# 4_Relays_Shutdown_TSAL.net
KiCad netlist of a schematic drawn in Altium Designer
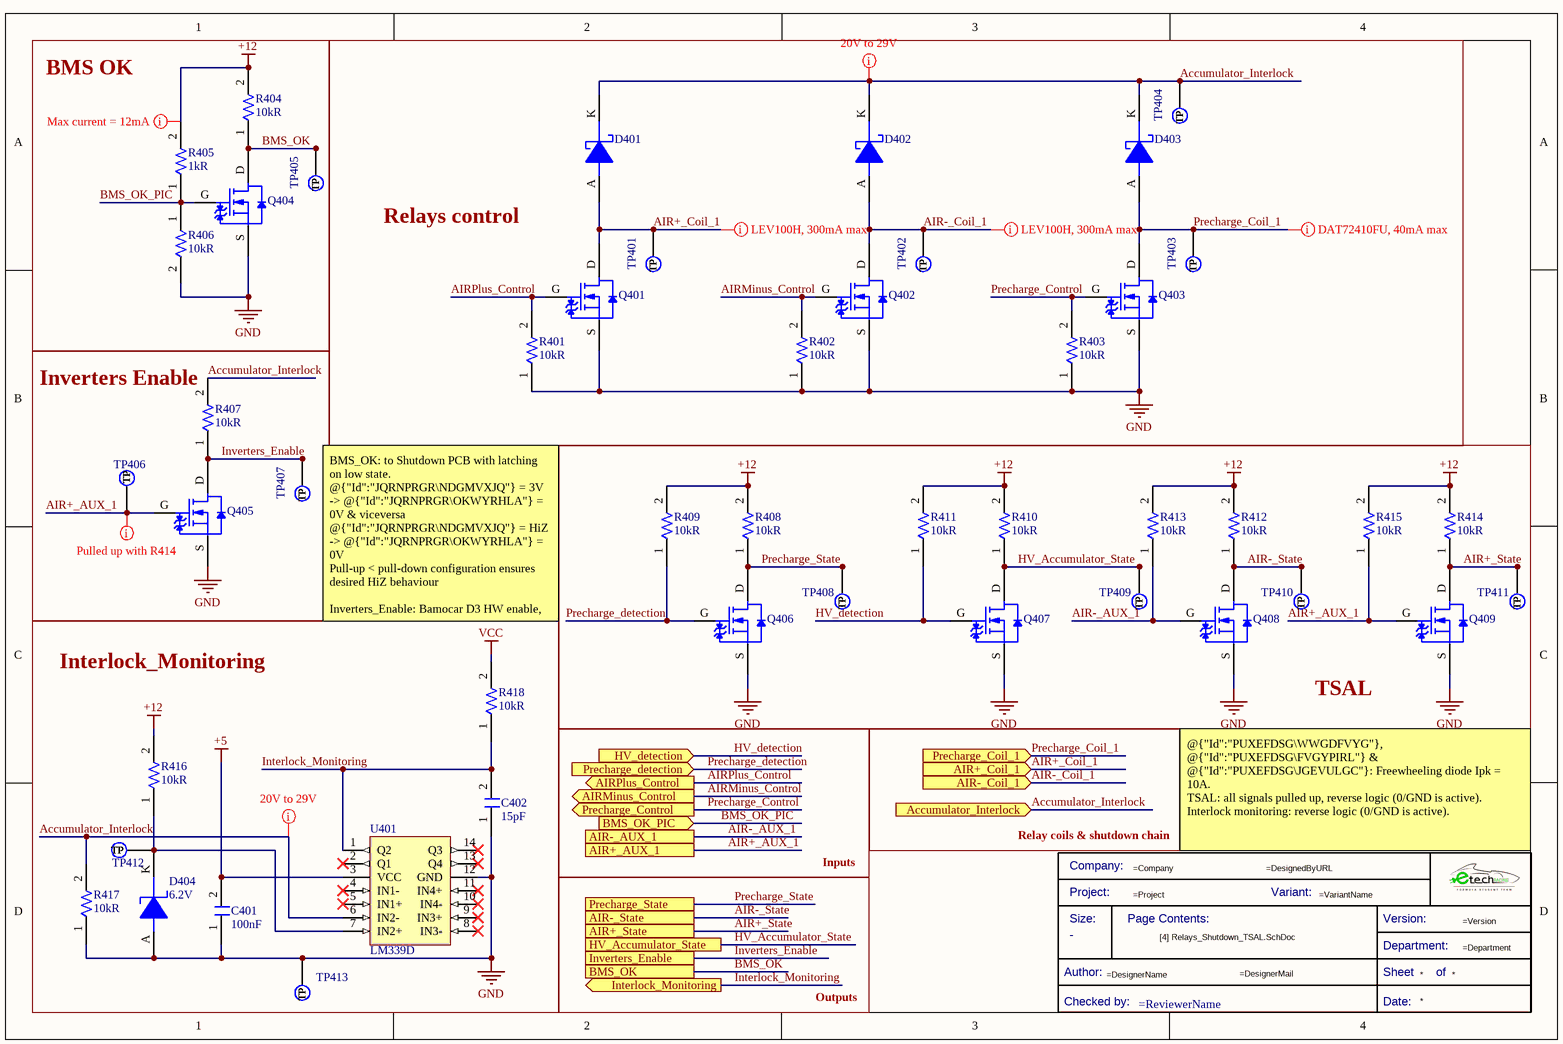
[diagram p0: [4] Relays_Shutdown_TSAL.SchDoc]

(export (version "E")
  (design (tool "Eeschema 10.0.6"))
  (components
    (comp (ref "*")
      (value "Title Block_template")
      (description "Standard Title Block")
      (fields (field (name "SIZE") "-"))
      (libsource (lib "e-Tech_Racing") (part "Title Block_template"))
    )
    (comp (ref "C401")
      (value "885012207098")
      (footprint "C0805FNPC-R")
      (description "Cap, 0.1ΜF, 50V, 10%, X7R, 0805")
      (fields
        (field (name "TOLERANCE") "10%")
        (field (name "CAPACITANCE") "100nF")
        (field (name ".CREATOR") "DR")
      )
      (libsource (lib "Passives") (part "C100n-50V-0805FNPC-X7R"))
    )
    (comp (ref "C402")
      (value "885012007052")
      (footprint "C0805FNPC-R")
      (description "Cap, 15PF, 50V, 5%, C0G/NP0, 0805")
      (fields
        (field (name "TOLERANCE") "5%")
        (field (name "CAPACITANCE") "15pF")
        (field (name ".CREATOR") "DR")
      )
      (libsource (lib "Passives") (part "C15p-50V-0805FNPC-NP0"))
    )
    (comp (ref "D401")
      (value "MBR0530")
      (footprint "DSC-SOD123")
      (description "VR=30V IF=500mA 30pF P=410mW")
      (fields (field (name ".CREATOR") "GP"))
      (libsource (lib "Filter components") (part "DSC-0.5/30-SOD123"))
    )
    (comp (ref "D402")
      (value "MBR0530")
      (footprint "DSC-SOD123")
      (description "VR=30V IF=500mA 30pF P=410mW")
      (fields (field (name ".CREATOR") "GP"))
      (libsource (lib "Filter components") (part "DSC-0.5/30-SOD123"))
    )
    (comp (ref "D403")
      (value "MBR0530")
      (footprint "DSC-SOD123")
      (description "VR=30V IF=500mA 30pF P=410mW")
      (fields (field (name ".CREATOR") "GP"))
      (libsource (lib "Filter components") (part "DSC-0.5/30-SOD123"))
    )
    (comp (ref "D404")
      (value "BZG05C6V2-E3-TR")
      (footprint "DZ-6.2V-DO-214AC")
      (description "BZG05C Series 6.2 V 200 mA Surface Mount Zener Diode - DO-214AC")
      (fields
        (field (name "TOLERANCE") "5%")
        (field (name "ZENER VOLTAGE") "6.2V")
        (field (name ".CREATOR") "DO")
      )
      (libsource (lib "Semiconductor") (part "DZ-6.2V-DO-214AC"))
    )
    (comp (ref "Q401")
      (value "CPH3455-TL-H")
      (footprint "TRT-NCH-3/35-CPH")
      (description "CPH3455-TL-H N-channel MOSFET Transistor; 3 A; 35 V; 3-Pin CPH")
      (fields (field (name "MANUFACTURER") "ON Semiconductor") (field (name ".CREATOR") "GP"))
      (libsource (lib "Semiconductor") (part "TRT-NCH-3/35-CPH"))
    )
    (comp (ref "Q402")
      (value "CPH3455-TL-H")
      (footprint "TRT-NCH-3/35-CPH")
      (description "CPH3455-TL-H N-channel MOSFET Transistor; 3 A; 35 V; 3-Pin CPH")
      (fields (field (name "MANUFACTURER") "ON Semiconductor") (field (name ".CREATOR") "GP"))
      (libsource (lib "Semiconductor") (part "TRT-NCH-3/35-CPH"))
    )
    (comp (ref "Q403")
      (value "CPH3455-TL-H")
      (footprint "TRT-NCH-3/35-CPH")
      (description "CPH3455-TL-H N-channel MOSFET Transistor; 3 A; 35 V; 3-Pin CPH")
      (fields (field (name "MANUFACTURER") "ON Semiconductor") (field (name ".CREATOR") "GP"))
      (libsource (lib "Semiconductor") (part "TRT-NCH-3/35-CPH"))
    )
    (comp (ref "Q404")
      (value "CPH3455-TL-H")
      (footprint "TRT-NCH-3/35-CPH")
      (description "CPH3455-TL-H N-channel MOSFET Transistor; 3 A; 35 V; 3-Pin CPH")
      (fields (field (name "MANUFACTURER") "ON Semiconductor") (field (name ".CREATOR") "GP"))
      (libsource (lib "Semiconductor") (part "TRT-NCH-3/35-CPH"))
    )
    (comp (ref "Q405")
      (value "CPH3455-TL-H")
      (footprint "TRT-NCH-3/35-CPH")
      (description "CPH3455-TL-H N-channel MOSFET Transistor; 3 A; 35 V; 3-Pin CPH")
      (fields (field (name "MANUFACTURER") "ON Semiconductor") (field (name ".CREATOR") "GP"))
      (libsource (lib "Semiconductor") (part "TRT-NCH-3/35-CPH"))
    )
    (comp (ref "Q406")
      (value "CPH3455-TL-H")
      (footprint "TRT-NCH-3/35-CPH")
      (description "CPH3455-TL-H N-channel MOSFET Transistor; 3 A; 35 V; 3-Pin CPH")
      (fields (field (name "MANUFACTURER") "ON Semiconductor") (field (name ".CREATOR") "GP"))
      (libsource (lib "Semiconductor") (part "TRT-NCH-3/35-CPH"))
    )
    (comp (ref "Q407")
      (value "CPH3455-TL-H")
      (footprint "TRT-NCH-3/35-CPH")
      (description "CPH3455-TL-H N-channel MOSFET Transistor; 3 A; 35 V; 3-Pin CPH")
      (fields (field (name "MANUFACTURER") "ON Semiconductor") (field (name ".CREATOR") "GP"))
      (libsource (lib "Semiconductor") (part "TRT-NCH-3/35-CPH"))
    )
    (comp (ref "Q408")
      (value "CPH3455-TL-H")
      (footprint "TRT-NCH-3/35-CPH")
      (description "CPH3455-TL-H N-channel MOSFET Transistor; 3 A; 35 V; 3-Pin CPH")
      (fields (field (name "MANUFACTURER") "ON Semiconductor") (field (name ".CREATOR") "GP"))
      (libsource (lib "Semiconductor") (part "TRT-NCH-3/35-CPH"))
    )
    (comp (ref "Q409")
      (value "CPH3455-TL-H")
      (footprint "TRT-NCH-3/35-CPH")
      (description "CPH3455-TL-H N-channel MOSFET Transistor; 3 A; 35 V; 3-Pin CPH")
      (fields (field (name "MANUFACTURER") "ON Semiconductor") (field (name ".CREATOR") "GP"))
      (libsource (lib "Semiconductor") (part "TRT-NCH-3/35-CPH"))
    )
    (comp (ref "R401")
      (value "CR0805-JW-103ELF")
      (footprint "R0805FTK")
      (fields
        (field (name "TOLERANCE") "5%")
        (field (name "RESISTANCE") "10kR")
        (field (name ".CREATOR") "DR")
      )
      (libsource (lib "Passives") (part "R10k-0805FTK"))
    )
    (comp (ref "R402")
      (value "CR0805-JW-103ELF")
      (footprint "R0805FTK")
      (fields
        (field (name "TOLERANCE") "5%")
        (field (name "RESISTANCE") "10kR")
        (field (name ".CREATOR") "DR")
      )
      (libsource (lib "Passives") (part "R10k-0805FTK"))
    )
    (comp (ref "R403")
      (value "CR0805-JW-103ELF")
      (footprint "R0805FTK")
      (fields
        (field (name "TOLERANCE") "5%")
        (field (name "RESISTANCE") "10kR")
        (field (name ".CREATOR") "DR")
      )
      (libsource (lib "Passives") (part "R10k-0805FTK"))
    )
    (comp (ref "R404")
      (value "CR0805-JW-103ELF")
      (footprint "R0805FTK")
      (fields
        (field (name "TOLERANCE") "5%")
        (field (name "RESISTANCE") "10kR")
        (field (name ".CREATOR") "DR")
      )
      (libsource (lib "Passives") (part "R10k-0805FTK"))
    )
    (comp (ref "R405")
      (value "CR0805-JW-102ELF")
      (footprint "R0805FTK")
      (description "Res Thick Film 0805 1K Ohm 5% 1/8W ±200ppm/°C Molded SMD SMD Paper Tape on Plastic Reel")
      (fields
        (field (name "TOLERANCE") "5%")
        (field (name "RESISTANCE") "1kR")
        (field (name ".CREATOR") "GP")
      )
      (libsource (lib "Passives") (part "R1k-0805FTK"))
    )
    (comp (ref "R406")
      (value "CR0805-JW-103ELF")
      (footprint "R0805FTK")
      (fields
        (field (name "TOLERANCE") "5%")
        (field (name "RESISTANCE") "10kR")
        (field (name ".CREATOR") "DR")
      )
      (libsource (lib "Passives") (part "R10k-0805FTK"))
    )
    (comp (ref "R407")
      (value "CR0805-JW-103ELF")
      (footprint "R0805FTK")
      (fields
        (field (name "TOLERANCE") "5%")
        (field (name "RESISTANCE") "10kR")
        (field (name ".CREATOR") "DR")
      )
      (libsource (lib "Passives") (part "R10k-0805FTK"))
    )
    (comp (ref "R408")
      (value "CR0805-JW-103ELF")
      (footprint "R0805FTK")
      (fields
        (field (name "TOLERANCE") "5%")
        (field (name "RESISTANCE") "10kR")
        (field (name ".CREATOR") "DR")
      )
      (libsource (lib "Passives") (part "R10k-0805FTK"))
    )
    (comp (ref "R409")
      (value "CR0805-JW-103ELF")
      (footprint "R0805FTK")
      (fields
        (field (name "TOLERANCE") "5%")
        (field (name "RESISTANCE") "10kR")
        (field (name ".CREATOR") "DR")
      )
      (libsource (lib "Passives") (part "R10k-0805FTK"))
    )
    (comp (ref "R410")
      (value "CR0805-JW-103ELF")
      (footprint "R0805FTK")
      (fields
        (field (name "TOLERANCE") "5%")
        (field (name "RESISTANCE") "10kR")
        (field (name ".CREATOR") "DR")
      )
      (libsource (lib "Passives") (part "R10k-0805FTK"))
    )
    (comp (ref "R411")
      (value "CR0805-JW-103ELF")
      (footprint "R0805FTK")
      (fields
        (field (name "TOLERANCE") "5%")
        (field (name "RESISTANCE") "10kR")
        (field (name ".CREATOR") "DR")
      )
      (libsource (lib "Passives") (part "R10k-0805FTK"))
    )
    (comp (ref "R412")
      (value "CR0805-JW-103ELF")
      (footprint "R0805FTK")
      (fields
        (field (name "TOLERANCE") "5%")
        (field (name "RESISTANCE") "10kR")
        (field (name ".CREATOR") "DR")
      )
      (libsource (lib "Passives") (part "R10k-0805FTK"))
    )
    (comp (ref "R413")
      (value "CR0805-JW-103ELF")
      (footprint "R0805FTK")
      (fields
        (field (name "TOLERANCE") "5%")
        (field (name "RESISTANCE") "10kR")
        (field (name ".CREATOR") "DR")
      )
      (libsource (lib "Passives") (part "R10k-0805FTK"))
    )
    (comp (ref "R414")
      (value "CR0805-JW-103ELF")
      (footprint "R0805FTK")
      (fields
        (field (name "TOLERANCE") "5%")
        (field (name "RESISTANCE") "10kR")
        (field (name ".CREATOR") "DR")
      )
      (libsource (lib "Passives") (part "R10k-0805FTK"))
    )
    (comp (ref "R415")
      (value "CR0805-JW-103ELF")
      (footprint "R0805FTK")
      (fields
        (field (name "TOLERANCE") "5%")
        (field (name "RESISTANCE") "10kR")
        (field (name ".CREATOR") "DR")
      )
      (libsource (lib "Passives") (part "R10k-0805FTK"))
    )
    (comp (ref "R416")
      (value "CR0805-JW-103ELF")
      (footprint "R0805FTK")
      (fields
        (field (name "TOLERANCE") "5%")
        (field (name "RESISTANCE") "10kR")
        (field (name ".CREATOR") "DR")
      )
      (libsource (lib "Passives") (part "R10k-0805FTK"))
    )
    (comp (ref "R417")
      (value "CR0805-JW-103ELF")
      (footprint "R0805FTK")
      (fields
        (field (name "TOLERANCE") "5%")
        (field (name "RESISTANCE") "10kR")
        (field (name ".CREATOR") "DR")
      )
      (libsource (lib "Passives") (part "R10k-0805FTK"))
    )
    (comp (ref "R418")
      (value "CR0805-JW-103ELF")
      (footprint "R0805FTK")
      (fields
        (field (name "TOLERANCE") "5%")
        (field (name "RESISTANCE") "10kR")
        (field (name ".CREATOR") "DR")
      )
      (libsource (lib "Passives") (part "R10k-0805FTK"))
    )
    (comp (ref "TP401")
      (value "TestPoint")
      (footprint "TestPoint")
      (description "Test Point 1x1 mm")
      (fields (field (name ".CREATOR") "GP") (field (name ".PCBCHECK") "GP") (field (name ".SCHCHECK") "GP"))
      (libsource (lib "e-Tech_Racing") (part "TestPoint"))
    )
    (comp (ref "TP402")
      (value "TestPoint")
      (footprint "TestPoint")
      (description "Test Point 1x1 mm")
      (fields (field (name ".CREATOR") "GP") (field (name ".PCBCHECK") "GP") (field (name ".SCHCHECK") "GP"))
      (libsource (lib "e-Tech_Racing") (part "TestPoint"))
    )
    (comp (ref "TP403")
      (value "TestPoint")
      (footprint "TestPoint")
      (description "Test Point 1x1 mm")
      (fields (field (name ".CREATOR") "GP") (field (name ".PCBCHECK") "GP") (field (name ".SCHCHECK") "GP"))
      (libsource (lib "e-Tech_Racing") (part "TestPoint"))
    )
    (comp (ref "TP404")
      (value "TestPoint")
      (footprint "TestPoint")
      (description "Test Point 1x1 mm")
      (fields (field (name ".CREATOR") "GP") (field (name ".PCBCHECK") "GP") (field (name ".SCHCHECK") "GP"))
      (libsource (lib "e-Tech_Racing") (part "TestPoint"))
    )
    (comp (ref "TP405")
      (value "TestPoint")
      (footprint "TestPoint")
      (description "Test Point 1x1 mm")
      (fields (field (name ".CREATOR") "GP") (field (name ".PCBCHECK") "GP") (field (name ".SCHCHECK") "GP"))
      (libsource (lib "e-Tech_Racing") (part "TestPoint"))
    )
    (comp (ref "TP406")
      (value "TestPoint")
      (footprint "TestPoint")
      (description "Test Point 1x1 mm")
      (fields (field (name ".CREATOR") "GP") (field (name ".PCBCHECK") "GP") (field (name ".SCHCHECK") "GP"))
      (libsource (lib "e-Tech_Racing") (part "TestPoint"))
    )
    (comp (ref "TP407")
      (value "TestPoint")
      (footprint "TestPoint")
      (description "Test Point 1x1 mm")
      (fields (field (name ".CREATOR") "GP") (field (name ".PCBCHECK") "GP") (field (name ".SCHCHECK") "GP"))
      (libsource (lib "e-Tech_Racing") (part "TestPoint"))
    )
    (comp (ref "TP408")
      (value "TestPoint")
      (footprint "TestPoint")
      (description "Test Point 1x1 mm")
      (fields (field (name ".CREATOR") "GP") (field (name ".PCBCHECK") "GP") (field (name ".SCHCHECK") "GP"))
      (libsource (lib "e-Tech_Racing") (part "TestPoint"))
    )
    (comp (ref "TP409")
      (value "TestPoint")
      (footprint "TestPoint")
      (description "Test Point 1x1 mm")
      (fields (field (name ".CREATOR") "GP") (field (name ".PCBCHECK") "GP") (field (name ".SCHCHECK") "GP"))
      (libsource (lib "e-Tech_Racing") (part "TestPoint"))
    )
    (comp (ref "TP410")
      (value "TestPoint")
      (footprint "TestPoint")
      (description "Test Point 1x1 mm")
      (fields (field (name ".CREATOR") "GP") (field (name ".PCBCHECK") "GP") (field (name ".SCHCHECK") "GP"))
      (libsource (lib "e-Tech_Racing") (part "TestPoint"))
    )
    (comp (ref "TP411")
      (value "TestPoint")
      (footprint "TestPoint")
      (description "Test Point 1x1 mm")
      (fields (field (name ".CREATOR") "GP") (field (name ".PCBCHECK") "GP") (field (name ".SCHCHECK") "GP"))
      (libsource (lib "e-Tech_Racing") (part "TestPoint"))
    )
    (comp (ref "TP412")
      (value "TestPoint")
      (footprint "TestPoint")
      (description "Test Point 1x1 mm")
      (fields (field (name ".CREATOR") "GP") (field (name ".PCBCHECK") "GP") (field (name ".SCHCHECK") "GP"))
      (libsource (lib "e-Tech_Racing") (part "TestPoint"))
    )
    (comp (ref "TP413")
      (value "TestPoint")
      (footprint "TestPoint")
      (description "Test Point 1x1 mm")
      (fields (field (name ".CREATOR") "GP") (field (name ".PCBCHECK") "GP") (field (name ".SCHCHECK") "GP"))
      (libsource (lib "e-Tech_Racing") (part "TestPoint"))
    )
    (comp (ref "U401")
      (value "LM339D")
      (footprint "Array_4_Amp_LM339D")
      (description "Comparator Quad ±18V/36V 14-Pin SOIC Tube")
      (fields
        (field (name "MANUFACTURER") "Texas Instruments")
        (field (name "MANUFACTURER PART NUMBER") "LM339D")
        (field (name ".CREATOR") "DO")
      )
      (libsource (lib "Integrated circuits") (part "Array_4_Amp_LM339D"))
    )
  )
  (nets
    (net (code "1") (name "+5") (class "Default")
      (node (ref "C401") (pin "2") (pinfunction "2_2") (pintype "passive"))
      (node (ref "U401") (pin "3") (pinfunction "VCC_3") (pintype "power_in"))
    )
    (net (code "2") (name "+12") (class "Default")
      (node (ref "R404") (pin "2") (pinfunction "2_2") (pintype "passive"))
      (node (ref "R405") (pin "2") (pinfunction "2_2") (pintype "passive"))
      (node (ref "R408") (pin "2") (pinfunction "2_2") (pintype "passive"))
      (node (ref "R409") (pin "2") (pinfunction "2_2") (pintype "passive"))
      (node (ref "R410") (pin "2") (pinfunction "2_2") (pintype "passive"))
      (node (ref "R411") (pin "2") (pinfunction "2_2") (pintype "passive"))
      (node (ref "R412") (pin "2") (pinfunction "2_2") (pintype "passive"))
      (node (ref "R413") (pin "2") (pinfunction "2_2") (pintype "passive"))
      (node (ref "R414") (pin "2") (pinfunction "2_2") (pintype "passive"))
      (node (ref "R415") (pin "2") (pinfunction "2_2") (pintype "passive"))
      (node (ref "R416") (pin "2") (pinfunction "2_2") (pintype "passive"))
    )
    (net (code "3") (name "/AIR+_AUX_1") (class "Default")
      (node (ref "Q405") (pin "G") (pinfunction "G_G") (pintype "passive"))
      (node (ref "Q409") (pin "G") (pinfunction "G_G") (pintype "passive"))
      (node (ref "R415") (pin "1") (pinfunction "1_1") (pintype "passive"))
      (node (ref "TP406") (pin "1") (pinfunction "TP_1") (pintype "passive"))
    )
    (net (code "4") (name "/AIR+_Coil_1") (class "Default")
      (node (ref "D401") (pin "A") (pinfunction "A_A") (pintype "passive"))
      (node (ref "Q401") (pin "D") (pinfunction "D_D") (pintype "passive"))
      (node (ref "TP401") (pin "1") (pinfunction "TP_1") (pintype "passive"))
    )
    (net (code "5") (name "/AIR+_State") (class "Default")
      (node (ref "Q409") (pin "D") (pinfunction "D_D") (pintype "passive"))
      (node (ref "R414") (pin "1") (pinfunction "1_1") (pintype "passive"))
      (node (ref "TP411") (pin "1") (pinfunction "TP_1") (pintype "passive"))
    )
    (net (code "6") (name "/AIR-_AUX_1") (class "Default")
      (node (ref "Q408") (pin "G") (pinfunction "G_G") (pintype "passive"))
      (node (ref "R413") (pin "1") (pinfunction "1_1") (pintype "passive"))
    )
    (net (code "7") (name "/AIR-_Coil_1") (class "Default")
      (node (ref "D402") (pin "A") (pinfunction "A_A") (pintype "passive"))
      (node (ref "Q402") (pin "D") (pinfunction "D_D") (pintype "passive"))
      (node (ref "TP402") (pin "1") (pinfunction "TP_1") (pintype "passive"))
    )
    (net (code "8") (name "/AIR-_State") (class "Default")
      (node (ref "Q408") (pin "D") (pinfunction "D_D") (pintype "passive"))
      (node (ref "R412") (pin "1") (pinfunction "1_1") (pintype "passive"))
      (node (ref "TP410") (pin "1") (pinfunction "TP_1") (pintype "passive"))
    )
    (net (code "9") (name "/AIRMinus_Control") (class "Default")
      (node (ref "Q402") (pin "G") (pinfunction "G_G") (pintype "passive"))
      (node (ref "R402") (pin "2") (pinfunction "2_2") (pintype "passive"))
    )
    (net (code "10") (name "/AIRPlus_Control") (class "Default")
      (node (ref "Q401") (pin "G") (pinfunction "G_G") (pintype "passive"))
      (node (ref "R401") (pin "2") (pinfunction "2_2") (pintype "passive"))
    )
    (net (code "11") (name "/Accumulator_Interlock") (class "Default")
      (node (ref "D401") (pin "K") (pinfunction "K_K") (pintype "passive"))
      (node (ref "D402") (pin "K") (pinfunction "K_K") (pintype "passive"))
      (node (ref "D403") (pin "K") (pinfunction "K_K") (pintype "passive"))
      (node (ref "R407") (pin "2") (pinfunction "2_2") (pintype "passive"))
      (node (ref "R417") (pin "2") (pinfunction "2_2") (pintype "passive"))
      (node (ref "TP404") (pin "1") (pinfunction "TP_1") (pintype "passive"))
      (node (ref "U401") (pin "6") (pinfunction "IN2-_6") (pintype "input"))
    )
    (net (code "12") (name "/BMS_OK") (class "Default")
      (node (ref "Q404") (pin "D") (pinfunction "D_D") (pintype "passive"))
      (node (ref "R404") (pin "1") (pinfunction "1_1") (pintype "passive"))
      (node (ref "TP405") (pin "1") (pinfunction "TP_1") (pintype "passive"))
    )
    (net (code "13") (name "/BMS_OK_PIC") (class "Default")
      (node (ref "Q404") (pin "G") (pinfunction "G_G") (pintype "passive"))
      (node (ref "R405") (pin "1") (pinfunction "1_1") (pintype "passive"))
      (node (ref "R406") (pin "1") (pinfunction "1_1") (pintype "passive"))
    )
    (net (code "14") (name "/HV_Accumulator_State") (class "Default")
      (node (ref "Q407") (pin "D") (pinfunction "D_D") (pintype "passive"))
      (node (ref "R410") (pin "1") (pinfunction "1_1") (pintype "passive"))
      (node (ref "TP409") (pin "1") (pinfunction "TP_1") (pintype "passive"))
    )
    (net (code "15") (name "/HV_detection") (class "Default")
      (node (ref "Q407") (pin "G") (pinfunction "G_G") (pintype "passive"))
      (node (ref "R411") (pin "1") (pinfunction "1_1") (pintype "passive"))
    )
    (net (code "16") (name "/Interlock_Monitoring") (class "Default")
      (node (ref "C402") (pin "2") (pinfunction "2_2") (pintype "passive"))
      (node (ref "R418") (pin "1") (pinfunction "1_1") (pintype "passive"))
      (node (ref "U401") (pin "1") (pinfunction "Q2_1") (pintype "output"))
    )
    (net (code "17") (name "/Inverters_Enable") (class "Default")
      (node (ref "Q405") (pin "D") (pinfunction "D_D") (pintype "passive"))
      (node (ref "R407") (pin "1") (pinfunction "1_1") (pintype "passive"))
      (node (ref "TP407") (pin "1") (pinfunction "TP_1") (pintype "passive"))
    )
    (net (code "18") (name "/Precharge_Coil_1") (class "Default")
      (node (ref "D403") (pin "A") (pinfunction "A_A") (pintype "passive"))
      (node (ref "Q403") (pin "D") (pinfunction "D_D") (pintype "passive"))
      (node (ref "TP403") (pin "1") (pinfunction "TP_1") (pintype "passive"))
    )
    (net (code "19") (name "/Precharge_Control") (class "Default")
      (node (ref "Q403") (pin "G") (pinfunction "G_G") (pintype "passive"))
      (node (ref "R403") (pin "2") (pinfunction "2_2") (pintype "passive"))
    )
    (net (code "20") (name "/Precharge_State") (class "Default")
      (node (ref "Q406") (pin "D") (pinfunction "D_D") (pintype "passive"))
      (node (ref "R408") (pin "1") (pinfunction "1_1") (pintype "passive"))
      (node (ref "TP408") (pin "1") (pinfunction "TP_1") (pintype "passive"))
    )
    (net (code "21") (name "/Precharge_detection") (class "Default")
      (node (ref "Q406") (pin "G") (pinfunction "G_G") (pintype "passive"))
      (node (ref "R409") (pin "1") (pinfunction "1_1") (pintype "passive"))
    )
    (net (code "22") (name "GND") (class "Default")
      (node (ref "C401") (pin "1") (pinfunction "1_1") (pintype "passive"))
      (node (ref "C402") (pin "1") (pinfunction "1_1") (pintype "passive"))
      (node (ref "D404") (pin "A") (pinfunction "A_A") (pintype "passive"))
      (node (ref "Q401") (pin "S") (pinfunction "S_S") (pintype "passive"))
      (node (ref "Q402") (pin "S") (pinfunction "S_S") (pintype "passive"))
      (node (ref "Q403") (pin "S") (pinfunction "S_S") (pintype "passive"))
      (node (ref "Q404") (pin "S") (pinfunction "S_S") (pintype "passive"))
      (node (ref "Q405") (pin "S") (pinfunction "S_S") (pintype "passive"))
      (node (ref "Q406") (pin "S") (pinfunction "S_S") (pintype "passive"))
      (node (ref "Q407") (pin "S") (pinfunction "S_S") (pintype "passive"))
      (node (ref "Q408") (pin "S") (pinfunction "S_S") (pintype "passive"))
      (node (ref "Q409") (pin "S") (pinfunction "S_S") (pintype "passive"))
      (node (ref "R401") (pin "1") (pinfunction "1_1") (pintype "passive"))
      (node (ref "R402") (pin "1") (pinfunction "1_1") (pintype "passive"))
      (node (ref "R403") (pin "1") (pinfunction "1_1") (pintype "passive"))
      (node (ref "R406") (pin "2") (pinfunction "2_2") (pintype "passive"))
      (node (ref "R417") (pin "1") (pinfunction "1_1") (pintype "passive"))
      (node (ref "TP413") (pin "1") (pinfunction "TP_1") (pintype "passive"))
      (node (ref "U401") (pin "12") (pinfunction "GND_12") (pintype "power_in"))
    )
    (net (code "23") (name "Net-(TP412-TP)") (class "Default")
      (node (ref "D404") (pin "K") (pinfunction "K_K") (pintype "passive"))
      (node (ref "R416") (pin "1") (pinfunction "1_1") (pintype "passive"))
      (node (ref "TP412") (pin "1") (pinfunction "TP_1") (pintype "passive"))
      (node (ref "U401") (pin "7") (pinfunction "IN2+_7") (pintype "input"))
    )
    (net (code "24") (name "VCC") (class "Default")
      (node (ref "R418") (pin "2") (pinfunction "2_2") (pintype "passive"))
    )
    (net (code "25") (name "unconnected-(U401-IN1+-Pad5)") (class "Default")
      (node (ref "U401") (pin "5") (pinfunction "IN1+_5") (pintype "input+no_connect"))
    )
    (net (code "26") (name "unconnected-(U401-IN1--Pad4)") (class "Default")
      (node (ref "U401") (pin "4") (pinfunction "IN1-_4") (pintype "input+no_connect"))
    )
    (net (code "27") (name "unconnected-(U401-IN3+-Pad9)") (class "Default")
      (node (ref "U401") (pin "9") (pinfunction "IN3+_9") (pintype "input+no_connect"))
    )
    (net (code "28") (name "unconnected-(U401-IN3--Pad8)") (class "Default")
      (node (ref "U401") (pin "8") (pinfunction "IN3-_8") (pintype "input+no_connect"))
    )
    (net (code "29") (name "unconnected-(U401-IN4+-Pad11)") (class "Default")
      (node (ref "U401") (pin "11") (pinfunction "IN4+_11") (pintype "input+no_connect"))
    )
    (net (code "30") (name "unconnected-(U401-IN4--Pad10)") (class "Default")
      (node (ref "U401") (pin "10") (pinfunction "IN4-_10") (pintype "input+no_connect"))
    )
    (net (code "31") (name "unconnected-(U401-Q1-Pad2)") (class "Default")
      (node (ref "U401") (pin "2") (pinfunction "Q1_2") (pintype "output+no_connect"))
    )
    (net (code "32") (name "unconnected-(U401-Q3-Pad14)") (class "Default")
      (node (ref "U401") (pin "14") (pinfunction "Q3_14") (pintype "output+no_connect"))
    )
    (net (code "33") (name "unconnected-(U401-Q4-Pad13)") (class "Default")
      (node (ref "U401") (pin "13") (pinfunction "Q4_13") (pintype "output+no_connect"))
    )
  )
)
